# IMU_board_V4.net
KiCad netlist of a schematic drawn in EAGLE
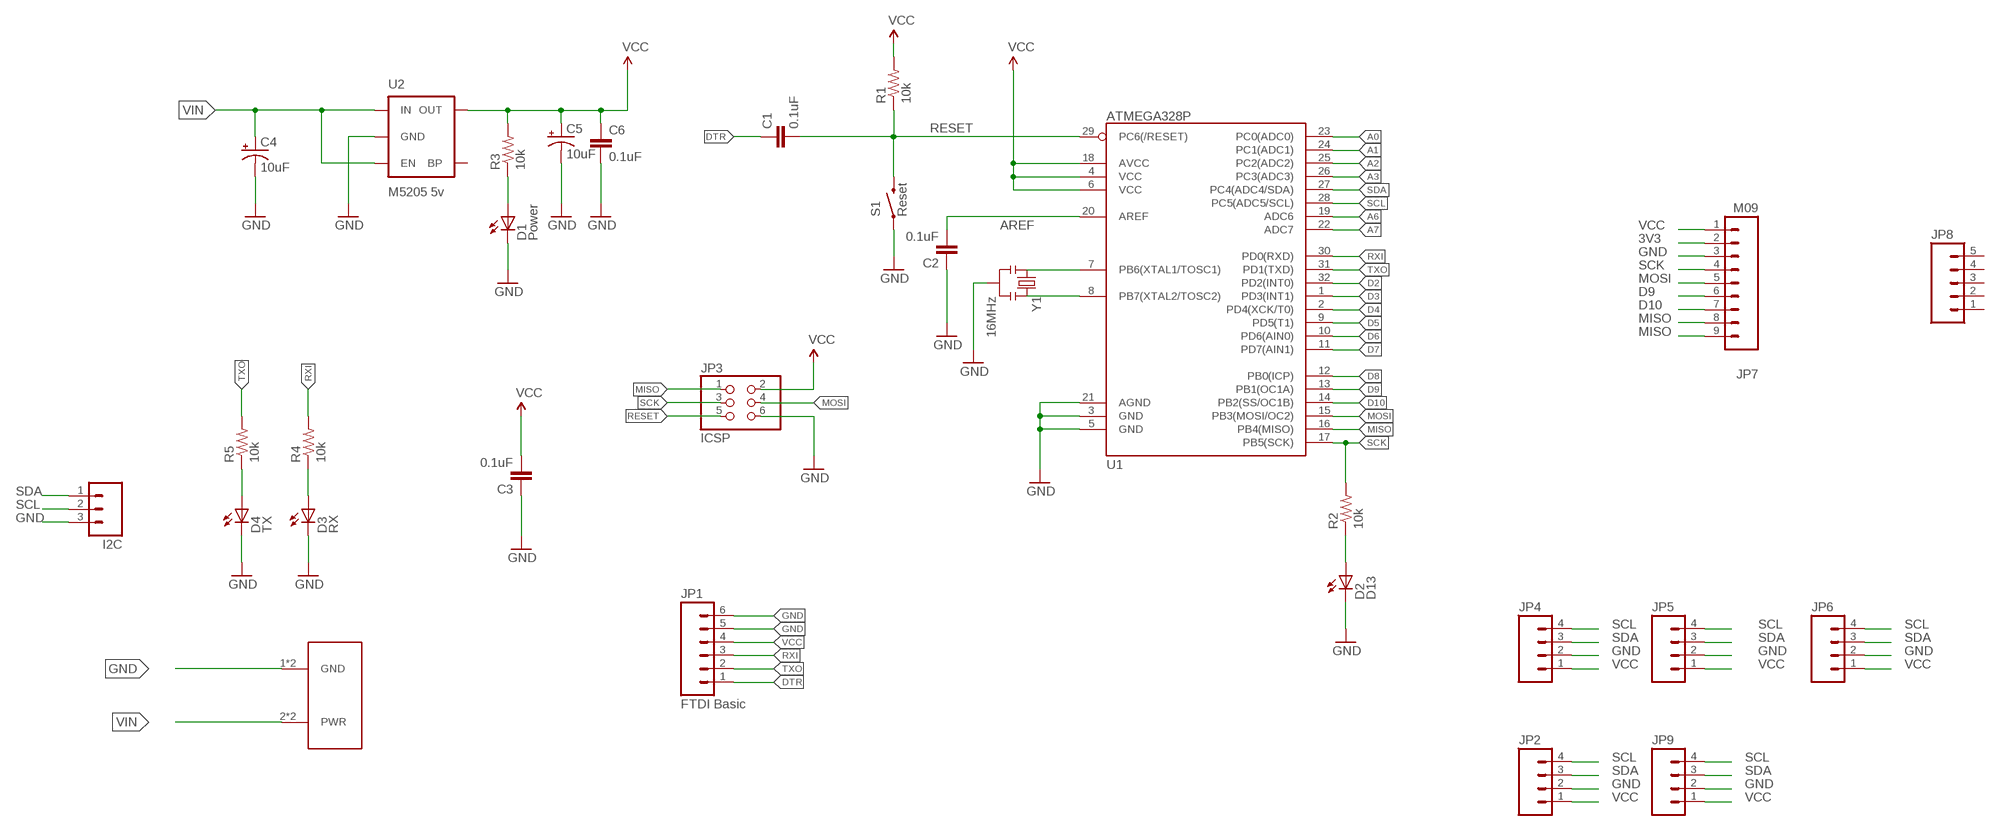
[diagram p0: schematic, sheet 1]

(export (version "E")
  (design (tool "Eeschema 10.0.6"))
  (components
    (comp (ref "C1")
      (value "0.1uF")
      (footprint "eagle-import:0603-CAP")
      (libsource (lib "eagle-import") (part "CAP0603-CAP"))
    )
    (comp (ref "C2")
      (value "0.1uF")
      (footprint "eagle-import:0603-CAP")
      (libsource (lib "eagle-import") (part "CAP0603-CAP"))
    )
    (comp (ref "C3")
      (value "0.1uF")
      (footprint "eagle-import:0603-CAP")
      (libsource (lib "eagle-import") (part "CAP0603-CAP"))
    )
    (comp (ref "C4")
      (value "10uF")
      (footprint "eagle-import:EIA3216")
      (libsource (lib "eagle-import") (part "CAP_POL1206"))
    )
    (comp (ref "C5")
      (value "10uF")
      (footprint "eagle-import:EIA3216")
      (libsource (lib "eagle-import") (part "CAP_POL1206"))
    )
    (comp (ref "C6")
      (value "0.1uF")
      (footprint "eagle-import:0603-CAP")
      (libsource (lib "eagle-import") (part "CAP0603-CAP"))
    )
    (comp (ref "D1")
      (value "Power")
      (footprint "eagle-import:LED-0603")
      (libsource (lib "eagle-import") (part "LED-RED0603"))
    )
    (comp (ref "D2")
      (value "D13")
      (footprint "eagle-import:LED-0603")
      (libsource (lib "eagle-import") (part "LED-RED0603"))
    )
    (comp (ref "D3")
      (value "RX")
      (footprint "eagle-import:LED-0603")
      (libsource (lib "eagle-import") (part "LED-GREEN0603"))
    )
    (comp (ref "D4")
      (value "TX")
      (footprint "eagle-import:LED-0603")
      (libsource (lib "eagle-import") (part "LED-RED0603"))
    )
    (comp (ref "I2C")
      (value "M03PTH")
      (footprint "eagle-import:1X03")
      (libsource (lib "eagle-import") (part "M03PTH"))
    )
    (comp (ref "JP1")
      (value "FTDI Basic")
      (footprint "eagle-import:1X06")
      (libsource (lib "eagle-import") (part "M06SIP"))
    )
    (comp (ref "JP2")
      (value "M04PTH")
      (footprint "eagle-import:1X04")
      (libsource (lib "eagle-import") (part "M04PTH"))
    )
    (comp (ref "JP3")
      (value "ICSP")
      (footprint "eagle-import:2X03")
      (libsource (lib "eagle-import") (part "PINHD-2X3"))
    )
    (comp (ref "JP4")
      (value "M04PTH")
      (footprint "eagle-import:1X04")
      (libsource (lib "eagle-import") (part "M04PTH"))
    )
    (comp (ref "JP5")
      (value "M04PTH")
      (footprint "eagle-import:1X04")
      (libsource (lib "eagle-import") (part "M04PTH"))
    )
    (comp (ref "JP6")
      (value "M04PTH")
      (footprint "eagle-import:1X04")
      (libsource (lib "eagle-import") (part "M04PTH"))
    )
    (comp (ref "JP7")
      (value "M09")
      (footprint "eagle-import:1X09")
      (libsource (lib "eagle-import") (part "M09"))
    )
    (comp (ref "JP8")
      (value "M05PTH")
      (footprint "eagle-import:1X05")
      (libsource (lib "eagle-import") (part "M05PTH"))
    )
    (comp (ref "JP9")
      (value "M04PTH")
      (footprint "eagle-import:1X04")
      (libsource (lib "eagle-import") (part "M04PTH"))
    )
    (comp (ref "R1")
      (value "10k")
      (footprint "eagle-import:0603-RES")
      (libsource (lib "eagle-import") (part "RESISTOR0603-RES"))
    )
    (comp (ref "R2")
      (value "10k")
      (footprint "eagle-import:0603-RES")
      (libsource (lib "eagle-import") (part "RESISTOR0603-RES"))
    )
    (comp (ref "R3")
      (value "10k")
      (footprint "eagle-import:0603-RES")
      (libsource (lib "eagle-import") (part "RESISTOR0603-RES"))
    )
    (comp (ref "R4")
      (value "10k")
      (footprint "eagle-import:0603-RES")
      (libsource (lib "eagle-import") (part "RESISTOR0603-RES"))
    )
    (comp (ref "R5")
      (value "10k")
      (footprint "eagle-import:0603-RES")
      (libsource (lib "eagle-import") (part "RESISTOR0603-RES"))
    )
    (comp (ref "S1")
      (value "Reset")
      (footprint "eagle-import:TACTILE_SWITCH_SMD")
      (libsource (lib "eagle-import") (part "SWITCH-MOMENTARY-2SMD"))
    )
    (comp (ref "U$1")
      (value "LSF-SMT")
      (footprint "eagle-import:LSF-SMT")
      (libsource (lib "eagle-import") (part "LSF-SMT"))
    )
    (comp (ref "U1")
      (value "ATMEGA328P")
      (footprint "eagle-import:TQFP32-08")
      (libsource (lib "eagle-import") (part "ATMEGA328_SMT"))
    )
    (comp (ref "U2")
      (value "M5205 5v")
      (footprint "eagle-import:SOT23-5")
      (libsource (lib "eagle-import") (part "MIC52055V"))
    )
    (comp (ref "Y1")
      (value "16MHz")
      (footprint "eagle-import:RESONATOR-SMD")
      (libsource (lib "eagle-import") (part "RESONATOR16MHZ"))
    )
  )
  (nets
    (net (code "1") (name "/3V3") (class "Default")
      (node (ref "JP7") (pin "2") (pinfunction "2_2") (pintype "passive"))
    )
    (net (code "2") (name "/AREF") (class "Default")
      (node (ref "C2") (pin "2") (pinfunction "2_2") (pintype "passive"))
      (node (ref "U1") (pin "20") (pinfunction "AREF_20") (pintype "bidirectional"))
    )
    (net (code "3") (name "A0") (class "Default")
      (node (ref "U1") (pin "23") (pinfunction "PC0(ADC0)_23") (pintype "bidirectional"))
    )
    (net (code "4") (name "A1") (class "Default")
      (node (ref "U1") (pin "24") (pinfunction "PC1(ADC1)_24") (pintype "bidirectional"))
    )
    (net (code "5") (name "A2") (class "Default")
      (node (ref "U1") (pin "25") (pinfunction "PC2(ADC2)_25") (pintype "bidirectional"))
    )
    (net (code "6") (name "A3") (class "Default")
      (node (ref "U1") (pin "26") (pinfunction "PC3(ADC3)_26") (pintype "bidirectional"))
    )
    (net (code "7") (name "A6") (class "Default")
      (node (ref "U1") (pin "19") (pinfunction "ADC6_19") (pintype "bidirectional"))
    )
    (net (code "8") (name "A7") (class "Default")
      (node (ref "U1") (pin "22") (pinfunction "ADC7_22") (pintype "bidirectional"))
    )
    (net (code "9") (name "D2") (class "Default")
      (node (ref "U1") (pin "32") (pinfunction "PD2(INT0)_32") (pintype "bidirectional"))
    )
    (net (code "10") (name "D3") (class "Default")
      (node (ref "U1") (pin "1") (pinfunction "PD3(INT1)_1") (pintype "bidirectional"))
    )
    (net (code "11") (name "D4") (class "Default")
      (node (ref "U1") (pin "2") (pinfunction "PD4(XCK/T0)_2") (pintype "bidirectional"))
    )
    (net (code "12") (name "D5") (class "Default")
      (node (ref "U1") (pin "9") (pinfunction "PD5(T1)_9") (pintype "bidirectional"))
    )
    (net (code "13") (name "D6") (class "Default")
      (node (ref "U1") (pin "10") (pinfunction "PD6(AIN0)_10") (pintype "bidirectional"))
    )
    (net (code "14") (name "D7") (class "Default")
      (node (ref "U1") (pin "11") (pinfunction "PD7(AIN1)_11") (pintype "bidirectional"))
    )
    (net (code "15") (name "D8") (class "Default")
      (node (ref "U1") (pin "12") (pinfunction "PB0(ICP)_12") (pintype "bidirectional"))
    )
    (net (code "16") (name "D9") (class "Default")
      (node (ref "JP7") (pin "6") (pinfunction "6_6") (pintype "passive"))
      (node (ref "U1") (pin "13") (pinfunction "PB1(OC1A)_13") (pintype "bidirectional"))
    )
    (net (code "17") (name "D10") (class "Default")
      (node (ref "JP7") (pin "7") (pinfunction "7_7") (pintype "passive"))
      (node (ref "U1") (pin "14") (pinfunction "PB2(SS/OC1B)_14") (pintype "bidirectional"))
    )
    (net (code "18") (name "DTR") (class "Default")
      (node (ref "C1") (pin "1") (pinfunction "1_1") (pintype "passive"))
      (node (ref "JP1") (pin "1") (pinfunction "1_1") (pintype "passive"))
    )
    (net (code "19") (name "GND") (class "Default")
      (node (ref "C2") (pin "1") (pinfunction "1_1") (pintype "passive"))
      (node (ref "C3") (pin "1") (pinfunction "1_1") (pintype "passive"))
      (node (ref "C4") (pin "C") (pinfunction "-_C") (pintype "passive"))
      (node (ref "C5") (pin "C") (pinfunction "-_C") (pintype "passive"))
      (node (ref "C6") (pin "2") (pinfunction "2_2") (pintype "passive"))
      (node (ref "D1") (pin "C") (pinfunction "C_C") (pintype "passive"))
      (node (ref "D2") (pin "C") (pinfunction "C_C") (pintype "passive"))
      (node (ref "D3") (pin "C") (pinfunction "C_C") (pintype "passive"))
      (node (ref "D4") (pin "C") (pinfunction "C_C") (pintype "passive"))
      (node (ref "I2C") (pin "3") (pinfunction "3_3") (pintype "passive"))
      (node (ref "JP1") (pin "5") (pinfunction "5_5") (pintype "passive"))
      (node (ref "JP1") (pin "6") (pinfunction "6_6") (pintype "passive"))
      (node (ref "JP2") (pin "2") (pinfunction "2_2") (pintype "passive"))
      (node (ref "JP3") (pin "6") (pinfunction "6_6") (pintype "passive"))
      (node (ref "JP4") (pin "2") (pinfunction "2_2") (pintype "passive"))
      (node (ref "JP5") (pin "2") (pinfunction "2_2") (pintype "passive"))
      (node (ref "JP6") (pin "2") (pinfunction "2_2") (pintype "passive"))
      (node (ref "JP7") (pin "3") (pinfunction "3_3") (pintype "passive"))
      (node (ref "JP9") (pin "2") (pinfunction "2_2") (pintype "passive"))
      (node (ref "S1") (pin "1") (pinfunction "1_1") (pintype "passive"))
      (node (ref "U$1") (pin "1") (pinfunction "GND_1") (pintype "bidirectional"))
      (node (ref "U$1") (pin "1-2") (pinfunction "GND_1-2") (pintype "bidirectional"))
      (node (ref "U1") (pin "21") (pinfunction "AGND_21") (pintype "bidirectional"))
      (node (ref "U1") (pin "3") (pinfunction "GND_3") (pintype "bidirectional"))
      (node (ref "U1") (pin "5") (pinfunction "GND_5") (pintype "bidirectional"))
      (node (ref "U2") (pin "2") (pinfunction "GND_2") (pintype "input"))
      (node (ref "Y1") (pin "2") (pinfunction "2_2") (pintype "passive"))
    )
    (net (code "20") (name "MISO") (class "Default")
      (node (ref "JP3") (pin "1") (pinfunction "1_1") (pintype "passive"))
      (node (ref "JP7") (pin "8") (pinfunction "8_8") (pintype "passive"))
      (node (ref "JP7") (pin "9") (pinfunction "9_9") (pintype "passive"))
      (node (ref "U1") (pin "16") (pinfunction "PB4(MISO)_16") (pintype "bidirectional"))
    )
    (net (code "21") (name "MOSI") (class "Default")
      (node (ref "JP3") (pin "4") (pinfunction "4_4") (pintype "passive"))
      (node (ref "JP7") (pin "5") (pinfunction "5_5") (pintype "passive"))
      (node (ref "U1") (pin "15") (pinfunction "PB3(MOSI/OC2)_15") (pintype "bidirectional"))
    )
    (net (code "22") (name "Net-(D1-PadA)") (class "Default")
      (node (ref "D1") (pin "A") (pinfunction "A_A") (pintype "passive"))
      (node (ref "R3") (pin "1") (pinfunction "1_1") (pintype "passive"))
    )
    (net (code "23") (name "Net-(D2-PadA)") (class "Default")
      (node (ref "D2") (pin "A") (pinfunction "A_A") (pintype "passive"))
      (node (ref "R2") (pin "1") (pinfunction "1_1") (pintype "passive"))
    )
    (net (code "24") (name "Net-(D3-PadA)") (class "Default")
      (node (ref "D3") (pin "A") (pinfunction "A_A") (pintype "passive"))
      (node (ref "R4") (pin "1") (pinfunction "1_1") (pintype "passive"))
    )
    (net (code "25") (name "Net-(D4-PadA)") (class "Default")
      (node (ref "D4") (pin "A") (pinfunction "A_A") (pintype "passive"))
      (node (ref "R5") (pin "1") (pinfunction "1_1") (pintype "passive"))
    )
    (net (code "26") (name "Net-(U1-PB6(XTAL1{slash}TOSC1))") (class "Default")
      (node (ref "U1") (pin "7") (pinfunction "PB6(XTAL1/TOSC1)_7") (pintype "bidirectional"))
      (node (ref "Y1") (pin "1") (pinfunction "1_1") (pintype "passive"))
    )
    (net (code "27") (name "Net-(U1-PB7(XTAL2{slash}TOSC2))") (class "Default")
      (node (ref "U1") (pin "8") (pinfunction "PB7(XTAL2/TOSC2)_8") (pintype "bidirectional"))
      (node (ref "Y1") (pin "3") (pinfunction "3_3") (pintype "passive"))
    )
    (net (code "28") (name "RESET") (class "Default")
      (node (ref "C1") (pin "2") (pinfunction "2_2") (pintype "passive"))
      (node (ref "JP3") (pin "5") (pinfunction "5_5") (pintype "passive"))
      (node (ref "R1") (pin "1") (pinfunction "1_1") (pintype "passive"))
      (node (ref "S1") (pin "3") (pinfunction "2_3") (pintype "passive"))
      (node (ref "U1") (pin "29") (pinfunction "PC6(/RESET)_29") (pintype "bidirectional"))
    )
    (net (code "29") (name "RXI") (class "Default")
      (node (ref "JP1") (pin "3") (pinfunction "3_3") (pintype "passive"))
      (node (ref "R4") (pin "2") (pinfunction "2_2") (pintype "passive"))
      (node (ref "U1") (pin "30") (pinfunction "PD0(RXD)_30") (pintype "bidirectional"))
    )
    (net (code "30") (name "SCK") (class "Default")
      (node (ref "JP3") (pin "3") (pinfunction "3_3") (pintype "passive"))
      (node (ref "JP7") (pin "4") (pinfunction "4_4") (pintype "passive"))
      (node (ref "R2") (pin "2") (pinfunction "2_2") (pintype "passive"))
      (node (ref "U1") (pin "17") (pinfunction "PB5(SCK)_17") (pintype "bidirectional"))
    )
    (net (code "31") (name "SCL") (class "Default")
      (node (ref "I2C") (pin "2") (pinfunction "2_2") (pintype "passive"))
      (node (ref "JP2") (pin "4") (pinfunction "4_4") (pintype "passive"))
      (node (ref "JP4") (pin "4") (pinfunction "4_4") (pintype "passive"))
      (node (ref "JP5") (pin "4") (pinfunction "4_4") (pintype "passive"))
      (node (ref "JP6") (pin "4") (pinfunction "4_4") (pintype "passive"))
      (node (ref "JP9") (pin "4") (pinfunction "4_4") (pintype "passive"))
      (node (ref "U1") (pin "28") (pinfunction "PC5(ADC5/SCL)_28") (pintype "bidirectional"))
    )
    (net (code "32") (name "SDA") (class "Default")
      (node (ref "I2C") (pin "1") (pinfunction "1_1") (pintype "passive"))
      (node (ref "JP2") (pin "3") (pinfunction "3_3") (pintype "passive"))
      (node (ref "JP4") (pin "3") (pinfunction "3_3") (pintype "passive"))
      (node (ref "JP5") (pin "3") (pinfunction "3_3") (pintype "passive"))
      (node (ref "JP6") (pin "3") (pinfunction "3_3") (pintype "passive"))
      (node (ref "JP9") (pin "3") (pinfunction "3_3") (pintype "passive"))
      (node (ref "U1") (pin "27") (pinfunction "PC4(ADC4/SDA)_27") (pintype "bidirectional"))
    )
    (net (code "33") (name "TXO") (class "Default")
      (node (ref "JP1") (pin "2") (pinfunction "2_2") (pintype "passive"))
      (node (ref "R5") (pin "2") (pinfunction "2_2") (pintype "passive"))
      (node (ref "U1") (pin "31") (pinfunction "PD1(TXD)_31") (pintype "bidirectional"))
    )
    (net (code "34") (name "VCC") (class "Default")
      (node (ref "C3") (pin "2") (pinfunction "2_2") (pintype "passive"))
      (node (ref "C5") (pin "A") (pinfunction "+_A") (pintype "passive"))
      (node (ref "C6") (pin "1") (pinfunction "1_1") (pintype "passive"))
      (node (ref "JP1") (pin "4") (pinfunction "4_4") (pintype "passive"))
      (node (ref "JP2") (pin "1") (pinfunction "1_1") (pintype "passive"))
      (node (ref "JP3") (pin "2") (pinfunction "2_2") (pintype "passive"))
      (node (ref "JP4") (pin "1") (pinfunction "1_1") (pintype "passive"))
      (node (ref "JP5") (pin "1") (pinfunction "1_1") (pintype "passive"))
      (node (ref "JP6") (pin "1") (pinfunction "1_1") (pintype "passive"))
      (node (ref "JP7") (pin "1") (pinfunction "1_1") (pintype "passive"))
      (node (ref "JP9") (pin "1") (pinfunction "1_1") (pintype "passive"))
      (node (ref "R1") (pin "2") (pinfunction "2_2") (pintype "passive"))
      (node (ref "R3") (pin "2") (pinfunction "2_2") (pintype "passive"))
      (node (ref "U1") (pin "18") (pinfunction "AVCC_18") (pintype "bidirectional"))
      (node (ref "U1") (pin "4") (pinfunction "VCC_4") (pintype "bidirectional"))
      (node (ref "U1") (pin "6") (pinfunction "VCC_6") (pintype "bidirectional"))
      (node (ref "U2") (pin "5") (pinfunction "OUT_5") (pintype "passive"))
    )
    (net (code "35") (name "VIN") (class "Default")
      (node (ref "C4") (pin "A") (pinfunction "+_A") (pintype "passive"))
      (node (ref "U$1") (pin "2") (pinfunction "PWR_2") (pintype "bidirectional"))
      (node (ref "U$1") (pin "2-2") (pinfunction "PWR_2-2") (pintype "bidirectional"))
      (node (ref "U2") (pin "1") (pinfunction "IN_1") (pintype "input"))
      (node (ref "U2") (pin "3") (pinfunction "EN_3") (pintype "input"))
    )
    (net (code "36") (name "unconnected-(JP8-Pad1)") (class "Default")
      (node (ref "JP8") (pin "1") (pinfunction "1_1") (pintype "passive"))
    )
    (net (code "37") (name "unconnected-(JP8-Pad2)") (class "Default")
      (node (ref "JP8") (pin "2") (pinfunction "2_2") (pintype "passive"))
    )
    (net (code "38") (name "unconnected-(JP8-Pad3)") (class "Default")
      (node (ref "JP8") (pin "3") (pinfunction "3_3") (pintype "passive"))
    )
    (net (code "39") (name "unconnected-(JP8-Pad4)") (class "Default")
      (node (ref "JP8") (pin "4") (pinfunction "4_4") (pintype "passive"))
    )
    (net (code "40") (name "unconnected-(JP8-Pad5)") (class "Default")
      (node (ref "JP8") (pin "5") (pinfunction "5_5") (pintype "passive"))
    )
    (net (code "41") (name "unconnected-(U2-BP-Pad4)") (class "Default")
      (node (ref "U2") (pin "4") (pinfunction "BP_4") (pintype "input"))
    )
  )
)
